# servoController.net
KiCad netlist of a schematic drawn in EAGLE
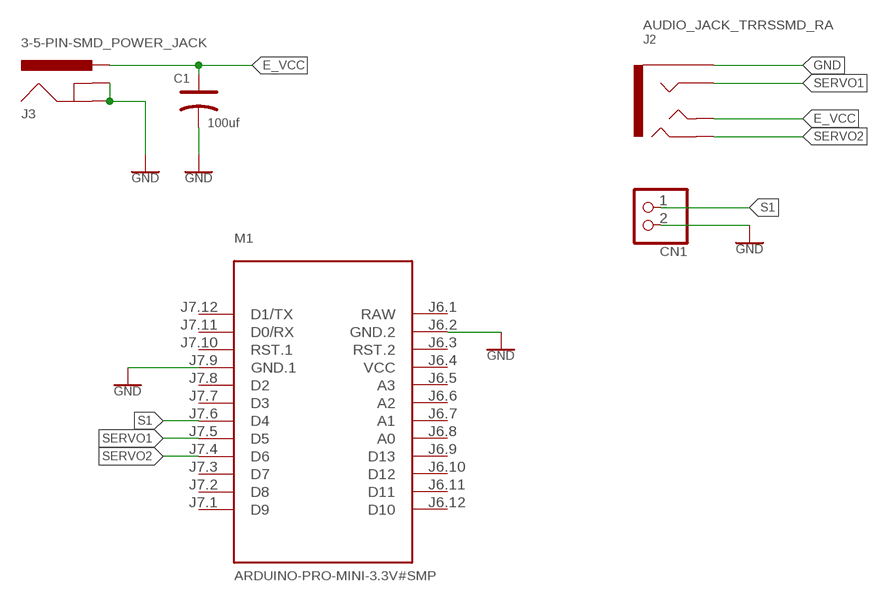
[diagram p0: schematic, sheet 1]

(export (version "E")
  (design (tool "Eeschema 10.0.6"))
  (components
    (comp (ref "C1")
      (value "100uf")
      (footprint "eagle-import:PC-D5.3MM")
      (fields (field (name "MPN") "KS 100uF/16V"))
      (libsource (lib "eagle-import") (part "DIP-ALUMINUM-47UF-16V(D5-H7MM)"))
    )
    (comp (ref "CN1")
      (value "ARDUINO_3V_TTL_INTERFACE_2_PI_ADAFRUIT_JST_2PIN-SMT-RA")
      (footprint "eagle-import:ARDUINO_3V_TTL_INTERFACE_2_PI_ADAFRUIT_JST-PH-2-SMT-RA")
      (libsource (lib "eagle-import") (part "ARDUINO_3V_TTL_INTERFACE_2_PI_ADAFRUIT_JST_2PIN-SMT-RA"))
    )
    (comp (ref "J2")
      (value "AUDIO_JACK_TRRSSMD_RA")
      (footprint "eagle-import:AUDIO_JACK_3.5MM_TRRS_SMD_RA")
      (libsource (lib "eagle-import") (part "AUDIO_JACK_TRRSSMD_RA"))
    )
    (comp (ref "J3")
      (value "3-5-PIN-SMD_POWER_JACK")
      (footprint "eagle-import:3-5-PIN-SMD_POWER_JACK_PTH")
      (libsource (lib "eagle-import") (part "3-5-PIN-SMD_POWER_JACK"))
    )
    (comp (ref "M1")
      (value "ARDUINO-PRO-MINI-3.3V#SMP")
      (footprint "eagle-import:ARDUINO-PRO-MINI#SMP")
      (libsource (lib "eagle-import") (part "ARDUINO-PRO-MINI-#SMP3.3V"))
    )
  )
  (nets
    (net (code "1") (name "/RAW") (class "Default")
      (node (ref "M1") (pin "J6.1") (pinfunction "RAW_J6.1") (pintype "power_in"))
    )
    (net (code "2") (name "/VCC") (class "Default")
      (node (ref "M1") (pin "J6.4") (pinfunction "VCC_J6.4") (pintype "power_in"))
    )
    (net (code "3") (name "E_VCC") (class "Default")
      (node (ref "C1") (pin "+") (pinfunction "+_+") (pintype "passive"))
      (node (ref "J2") (pin "TIP") (pinfunction "TIP_TIP") (pintype "bidirectional"))
      (node (ref "J3") (pin "PWR") (pinfunction "PWR_PWR") (pintype "bidirectional"))
    )
    (net (code "4") (name "GND") (class "Default")
      (node (ref "C1") (pin "-") (pinfunction "-_-") (pintype "passive"))
      (node (ref "CN1") (pin "2") (pinfunction "1_2") (pintype "passive"))
      (node (ref "J2") (pin "EARTH") (pinfunction "EARTH_EARTH") (pintype "bidirectional"))
      (node (ref "J3") (pin "GND") (pinfunction "GND_GND") (pintype "bidirectional"))
      (node (ref "J3") (pin "GNDBREAK") (pinfunction "GNDBREAK_GNDBREAK") (pintype "bidirectional"))
      (node (ref "M1") (pin "J6.2") (pinfunction "GND.2_J6.2") (pintype "power_in"))
      (node (ref "M1") (pin "J7.9") (pinfunction "GND.1_J7.9") (pintype "power_in"))
    )
    (net (code "5") (name "S1") (class "Default")
      (node (ref "CN1") (pin "1") (pinfunction "2_1") (pintype "passive"))
      (node (ref "M1") (pin "J7.6") (pinfunction "D4_J7.6") (pintype "bidirectional"))
    )
    (net (code "6") (name "SERVO1") (class "Default")
      (node (ref "J2") (pin "RING1") (pinfunction "RING1_RING1") (pintype "bidirectional"))
      (node (ref "M1") (pin "J7.5") (pinfunction "D5_J7.5") (pintype "bidirectional"))
    )
    (net (code "7") (name "SERVO2") (class "Default")
      (node (ref "J2") (pin "RING2") (pinfunction "RING2_RING2") (pintype "bidirectional"))
      (node (ref "M1") (pin "J7.4") (pinfunction "D6_J7.4") (pintype "bidirectional"))
    )
    (net (code "8") (name "unconnected-(M1-A0-PadJ6.8)") (class "Default")
      (node (ref "M1") (pin "J6.8") (pinfunction "A0_J6.8") (pintype "bidirectional"))
    )
    (net (code "9") (name "unconnected-(M1-A1-PadJ6.7)") (class "Default")
      (node (ref "M1") (pin "J6.7") (pinfunction "A1_J6.7") (pintype "bidirectional"))
    )
    (net (code "10") (name "unconnected-(M1-A2-PadJ6.6)") (class "Default")
      (node (ref "M1") (pin "J6.6") (pinfunction "A2_J6.6") (pintype "bidirectional"))
    )
    (net (code "11") (name "unconnected-(M1-A3-PadJ6.5)") (class "Default")
      (node (ref "M1") (pin "J6.5") (pinfunction "A3_J6.5") (pintype "bidirectional"))
    )
    (net (code "12") (name "unconnected-(M1-D0{slash}RX-PadJ7.11)") (class "Default")
      (node (ref "M1") (pin "J7.11") (pinfunction "D0/RX_J7.11") (pintype "bidirectional"))
    )
    (net (code "13") (name "unconnected-(M1-D1{slash}TX-PadJ7.12)") (class "Default")
      (node (ref "M1") (pin "J7.12") (pinfunction "D1/TX_J7.12") (pintype "bidirectional"))
    )
    (net (code "14") (name "unconnected-(M1-D2-PadJ7.8)") (class "Default")
      (node (ref "M1") (pin "J7.8") (pinfunction "D2_J7.8") (pintype "bidirectional"))
    )
    (net (code "15") (name "unconnected-(M1-D3-PadJ7.7)") (class "Default")
      (node (ref "M1") (pin "J7.7") (pinfunction "D3_J7.7") (pintype "bidirectional"))
    )
    (net (code "16") (name "unconnected-(M1-D7-PadJ7.3)") (class "Default")
      (node (ref "M1") (pin "J7.3") (pinfunction "D7_J7.3") (pintype "bidirectional"))
    )
    (net (code "17") (name "unconnected-(M1-D8-PadJ7.2)") (class "Default")
      (node (ref "M1") (pin "J7.2") (pinfunction "D8_J7.2") (pintype "bidirectional"))
    )
    (net (code "18") (name "unconnected-(M1-D9-PadJ7.1)") (class "Default")
      (node (ref "M1") (pin "J7.1") (pinfunction "D9_J7.1") (pintype "bidirectional"))
    )
    (net (code "19") (name "unconnected-(M1-D10-PadJ6.12)") (class "Default")
      (node (ref "M1") (pin "J6.12") (pinfunction "D10_J6.12") (pintype "bidirectional"))
    )
    (net (code "20") (name "unconnected-(M1-D11-PadJ6.11)") (class "Default")
      (node (ref "M1") (pin "J6.11") (pinfunction "D11_J6.11") (pintype "bidirectional"))
    )
    (net (code "21") (name "unconnected-(M1-D12-PadJ6.10)") (class "Default")
      (node (ref "M1") (pin "J6.10") (pinfunction "D12_J6.10") (pintype "bidirectional"))
    )
    (net (code "22") (name "unconnected-(M1-D13-PadJ6.9)") (class "Default")
      (node (ref "M1") (pin "J6.9") (pinfunction "D13_J6.9") (pintype "bidirectional"))
    )
    (net (code "23") (name "unconnected-(M1-RST.1-PadJ7.10)") (class "Default")
      (node (ref "M1") (pin "J7.10") (pinfunction "RST.1_J7.10") (pintype "bidirectional"))
    )
    (net (code "24") (name "unconnected-(M1-RST.2-PadJ6.3)") (class "Default")
      (node (ref "M1") (pin "J6.3") (pinfunction "RST.2_J6.3") (pintype "bidirectional"))
    )
  )
)
